# active_filter_2500Hz.net
KiCad netlist of a schematic drawn in Altium Designer
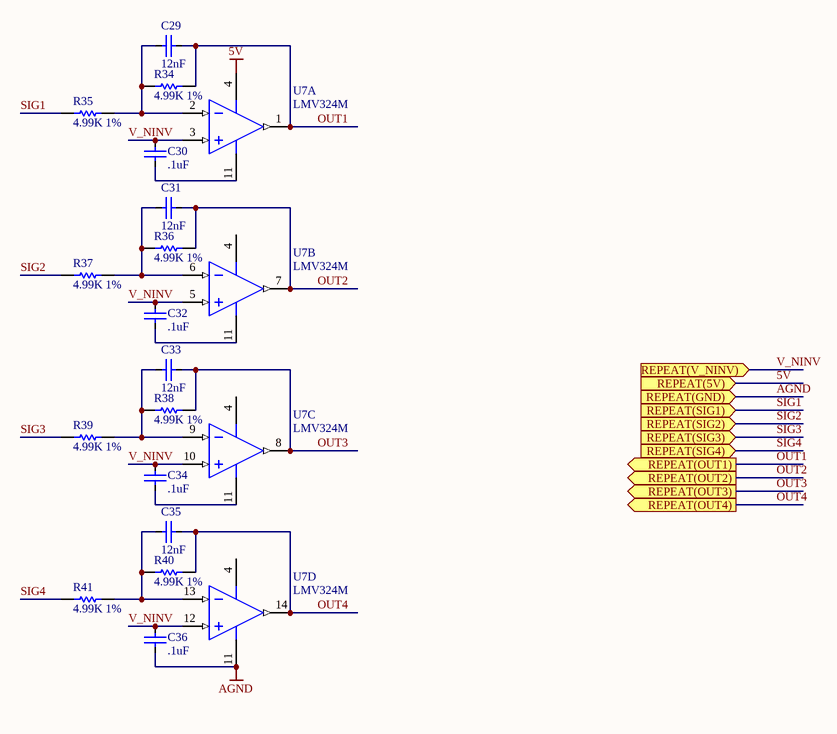
[diagram p0: active_filter_2500Hz.SchDoc]

(export (version "E")
  (design (tool "Eeschema 10.0.6"))
  (components
    (comp (ref "C29")
      (value "12nF")
      (footprint "0603 (1608)")
      (fields
        (field (name "MANUFACTURER") "Murata")
        (field (name "PART NO.") "490-1513-1-ND")
        (field (name "Comment") "Capacitor")
      )
      (libsource (lib "SMT Chip") (part "Capacitor"))
    )
    (comp (ref "C30")
      (value ".1uF")
      (footprint "0603 (1608)")
      (fields
        (field (name "MANUFACTURER") "Murata")
        (field (name "PART NO.") "490-1524-1-ND")
        (field (name "Comment") "Capacitor")
      )
      (libsource (lib "SMT Chip") (part "Capacitor"))
    )
    (comp (ref "C31")
      (value "12nF")
      (footprint "0603 (1608)")
      (fields
        (field (name "MANUFACTURER") "Murata")
        (field (name "PART NO.") "490-1513-1-ND")
        (field (name "Comment") "Capacitor")
      )
      (libsource (lib "SMT Chip") (part "Capacitor"))
    )
    (comp (ref "C32")
      (value ".1uF")
      (footprint "0603 (1608)")
      (fields
        (field (name "MANUFACTURER") "Murata")
        (field (name "PART NO.") "490-1524-1-ND")
        (field (name "Comment") "Capacitor")
      )
      (libsource (lib "SMT Chip") (part "Capacitor"))
    )
    (comp (ref "C33")
      (value "12nF")
      (footprint "0603 (1608)")
      (fields
        (field (name "MANUFACTURER") "Murata")
        (field (name "PART NO.") "490-1513-1-ND")
        (field (name "Comment") "Capacitor")
      )
      (libsource (lib "SMT Chip") (part "Capacitor"))
    )
    (comp (ref "C34")
      (value ".1uF")
      (footprint "0603 (1608)")
      (fields
        (field (name "MANUFACTURER") "Murata")
        (field (name "PART NO.") "490-1524-1-ND")
        (field (name "Comment") "Capacitor")
      )
      (libsource (lib "SMT Chip") (part "Capacitor"))
    )
    (comp (ref "C35")
      (value "12nF")
      (footprint "0603 (1608)")
      (fields
        (field (name "MANUFACTURER") "Murata")
        (field (name "PART NO.") "490-1513-1-ND")
        (field (name "Comment") "Capacitor")
      )
      (libsource (lib "SMT Chip") (part "Capacitor"))
    )
    (comp (ref "C36")
      (value ".1uF")
      (footprint "0603 (1608)")
      (fields
        (field (name "MANUFACTURER") "Murata")
        (field (name "PART NO.") "490-1524-1-ND")
        (field (name "Comment") "Capacitor")
      )
      (libsource (lib "SMT Chip") (part "Capacitor"))
    )
    (comp (ref "R34")
      (value "4.99K 1%")
      (footprint "0603 (1608)")
      (description "Resistor")
      (fields (field (name "PART NO.") "P4.99KHCT-ND") (field (name "Comment") "Res1"))
      (libsource (lib "Miscellaneous Devices") (part "Res1"))
    )
    (comp (ref "R35")
      (value "4.99K 1%")
      (footprint "0603 (1608)")
      (description "Resistor")
      (fields (field (name "PART NO.") "P4.99KHCT-ND") (field (name "Comment") "Res1"))
      (libsource (lib "Miscellaneous Devices") (part "Res1"))
    )
    (comp (ref "R36")
      (value "4.99K 1%")
      (footprint "0603 (1608)")
      (description "Resistor")
      (fields (field (name "PART NO.") "P4.99KHCT-ND") (field (name "Comment") "Res1"))
      (libsource (lib "Miscellaneous Devices") (part "Res1"))
    )
    (comp (ref "R37")
      (value "4.99K 1%")
      (footprint "0603 (1608)")
      (description "Resistor")
      (fields (field (name "PART NO.") "P4.99KHCT-ND") (field (name "Comment") "Res1"))
      (libsource (lib "Miscellaneous Devices") (part "Res1"))
    )
    (comp (ref "R38")
      (value "4.99K 1%")
      (footprint "0603 (1608)")
      (description "Resistor")
      (fields (field (name "PART NO.") "P4.99KHCT-ND") (field (name "Comment") "Res1"))
      (libsource (lib "Miscellaneous Devices") (part "Res1"))
    )
    (comp (ref "R39")
      (value "4.99K 1%")
      (footprint "0603 (1608)")
      (description "Resistor")
      (fields (field (name "PART NO.") "P4.99KHCT-ND") (field (name "Comment") "Res1"))
      (libsource (lib "Miscellaneous Devices") (part "Res1"))
    )
    (comp (ref "R40")
      (value "4.99K 1%")
      (footprint "0603 (1608)")
      (description "Resistor")
      (fields (field (name "PART NO.") "P4.99KHCT-ND") (field (name "Comment") "Res1"))
      (libsource (lib "Miscellaneous Devices") (part "Res1"))
    )
    (comp (ref "R41")
      (value "4.99K 1%")
      (footprint "0603 (1608)")
      (description "Resistor")
      (fields (field (name "PART NO.") "P4.99KHCT-ND") (field (name "Comment") "Res1"))
      (libsource (lib "Miscellaneous Devices") (part "Res1"))
    )
    (comp (ref "U7")
      (value "LMV324M")
      (footprint "M14A_N")
      (description "General Purpose, Low Voltage, Rail-to-Rail Output Operational Amplifiers")
      (fields
        (field (name "MANUFACTURER") "National Semiconductor")
        (field (name "DIGIKEYPARTNUMBER") "LMV324MXCT-ND")
        (field (name "PUBLISHER") "Altium Limited")
      )
      (libsource (lib "NSC Amplifier") (part "LMV324M"))
    )
  )
  (nets
    (net (code "1") (name "/OUT1") (class "Default")
      (node (ref "C29") (pin "2") (pinfunction "2_2") (pintype "passive"))
      (node (ref "R34") (pin "1") (pinfunction "1_1") (pintype "passive"))
      (node (ref "U7") (pin "1") (pinfunction "OUTA_1") (pintype "output"))
    )
    (net (code "2") (name "/OUT2") (class "Default")
      (node (ref "C31") (pin "2") (pinfunction "2_2") (pintype "passive"))
      (node (ref "R36") (pin "1") (pinfunction "1_1") (pintype "passive"))
      (node (ref "U7") (pin "7") (pinfunction "OUTB_7") (pintype "output"))
    )
    (net (code "3") (name "/OUT3") (class "Default")
      (node (ref "C33") (pin "2") (pinfunction "2_2") (pintype "passive"))
      (node (ref "R38") (pin "1") (pinfunction "1_1") (pintype "passive"))
      (node (ref "U7") (pin "8") (pinfunction "OUTC_8") (pintype "output"))
    )
    (net (code "4") (name "/OUT4") (class "Default")
      (node (ref "C35") (pin "2") (pinfunction "2_2") (pintype "passive"))
      (node (ref "R40") (pin "1") (pinfunction "1_1") (pintype "passive"))
      (node (ref "U7") (pin "14") (pinfunction "OUTD_14") (pintype "output"))
    )
    (net (code "5") (name "/SIG1") (class "Default")
      (node (ref "R35") (pin "2") (pinfunction "2_2") (pintype "passive"))
    )
    (net (code "6") (name "/SIG2") (class "Default")
      (node (ref "R37") (pin "2") (pinfunction "2_2") (pintype "passive"))
    )
    (net (code "7") (name "/SIG3") (class "Default")
      (node (ref "R39") (pin "2") (pinfunction "2_2") (pintype "passive"))
    )
    (net (code "8") (name "/SIG4") (class "Default")
      (node (ref "R41") (pin "2") (pinfunction "2_2") (pintype "passive"))
    )
    (net (code "9") (name "/V_NINV") (class "Default")
      (node (ref "C30") (pin "1") (pinfunction "1_1") (pintype "passive"))
      (node (ref "C32") (pin "1") (pinfunction "1_1") (pintype "passive"))
      (node (ref "C34") (pin "1") (pinfunction "1_1") (pintype "passive"))
      (node (ref "C36") (pin "1") (pinfunction "1_1") (pintype "passive"))
      (node (ref "U7") (pin "10") (pinfunction "INC+_10") (pintype "input"))
      (node (ref "U7") (pin "12") (pinfunction "IND+_12") (pintype "input"))
      (node (ref "U7") (pin "3") (pinfunction "INA+_3") (pintype "input"))
      (node (ref "U7") (pin "5") (pinfunction "INB+_5") (pintype "input"))
    )
    (net (code "10") (name "5V") (class "Default")
      (node (ref "U7") (pin "4") (pinfunction "V+_4") (pintype "power_in"))
    )
    (net (code "11") (name "AGND") (class "Default")
      (node (ref "C36") (pin "2") (pinfunction "2_2") (pintype "passive"))
      (node (ref "U7") (pin "11") (pinfunction "V-_11") (pintype "power_in"))
    )
    (net (code "12") (name "Net-(U7A-INA-)") (class "Default")
      (node (ref "C29") (pin "1") (pinfunction "1_1") (pintype "passive"))
      (node (ref "R34") (pin "2") (pinfunction "2_2") (pintype "passive"))
      (node (ref "R35") (pin "1") (pinfunction "1_1") (pintype "passive"))
      (node (ref "U7") (pin "2") (pinfunction "INA-_2") (pintype "input"))
    )
    (net (code "13") (name "Net-(U7A-V-)") (class "Default")
      (node (ref "C30") (pin "2") (pinfunction "2_2") (pintype "passive"))
      (node (ref "U7") (pin "11") (pinfunction "V-_11") (pintype "power_in"))
    )
    (net (code "14") (name "Net-(U7B-INB-)") (class "Default")
      (node (ref "C31") (pin "1") (pinfunction "1_1") (pintype "passive"))
      (node (ref "R36") (pin "2") (pinfunction "2_2") (pintype "passive"))
      (node (ref "R37") (pin "1") (pinfunction "1_1") (pintype "passive"))
      (node (ref "U7") (pin "6") (pinfunction "INB-_6") (pintype "input"))
    )
    (net (code "15") (name "Net-(U7B-V-)") (class "Default")
      (node (ref "C32") (pin "2") (pinfunction "2_2") (pintype "passive"))
      (node (ref "U7") (pin "11") (pinfunction "V-_11") (pintype "power_in"))
    )
    (net (code "16") (name "Net-(U7C-INC-)") (class "Default")
      (node (ref "C33") (pin "1") (pinfunction "1_1") (pintype "passive"))
      (node (ref "R38") (pin "2") (pinfunction "2_2") (pintype "passive"))
      (node (ref "R39") (pin "1") (pinfunction "1_1") (pintype "passive"))
      (node (ref "U7") (pin "9") (pinfunction "INC-_9") (pintype "input"))
    )
    (net (code "17") (name "Net-(U7C-V-)") (class "Default")
      (node (ref "C34") (pin "2") (pinfunction "2_2") (pintype "passive"))
      (node (ref "U7") (pin "11") (pinfunction "V-_11") (pintype "power_in"))
    )
    (net (code "18") (name "Net-(U7D-IND-)") (class "Default")
      (node (ref "C35") (pin "1") (pinfunction "1_1") (pintype "passive"))
      (node (ref "R40") (pin "2") (pinfunction "2_2") (pintype "passive"))
      (node (ref "R41") (pin "1") (pinfunction "1_1") (pintype "passive"))
      (node (ref "U7") (pin "13") (pinfunction "IND-_13") (pintype "input"))
    )
    (net (code "19") (name "unconnected-(U7B-V+-Pad4)") (class "Default")
      (node (ref "U7") (pin "4") (pinfunction "V+_4") (pintype "power_in"))
    )
    (net (code "20") (name "unconnected-(U7C-V+-Pad4)") (class "Default")
      (node (ref "U7") (pin "4") (pinfunction "V+_4") (pintype "power_in"))
    )
    (net (code "21") (name "unconnected-(U7D-V+-Pad4)") (class "Default")
      (node (ref "U7") (pin "4") (pinfunction "V+_4") (pintype "power_in"))
    )
  )
)
